# Connectors.net
KiCad netlist of a schematic drawn in Altium Designer
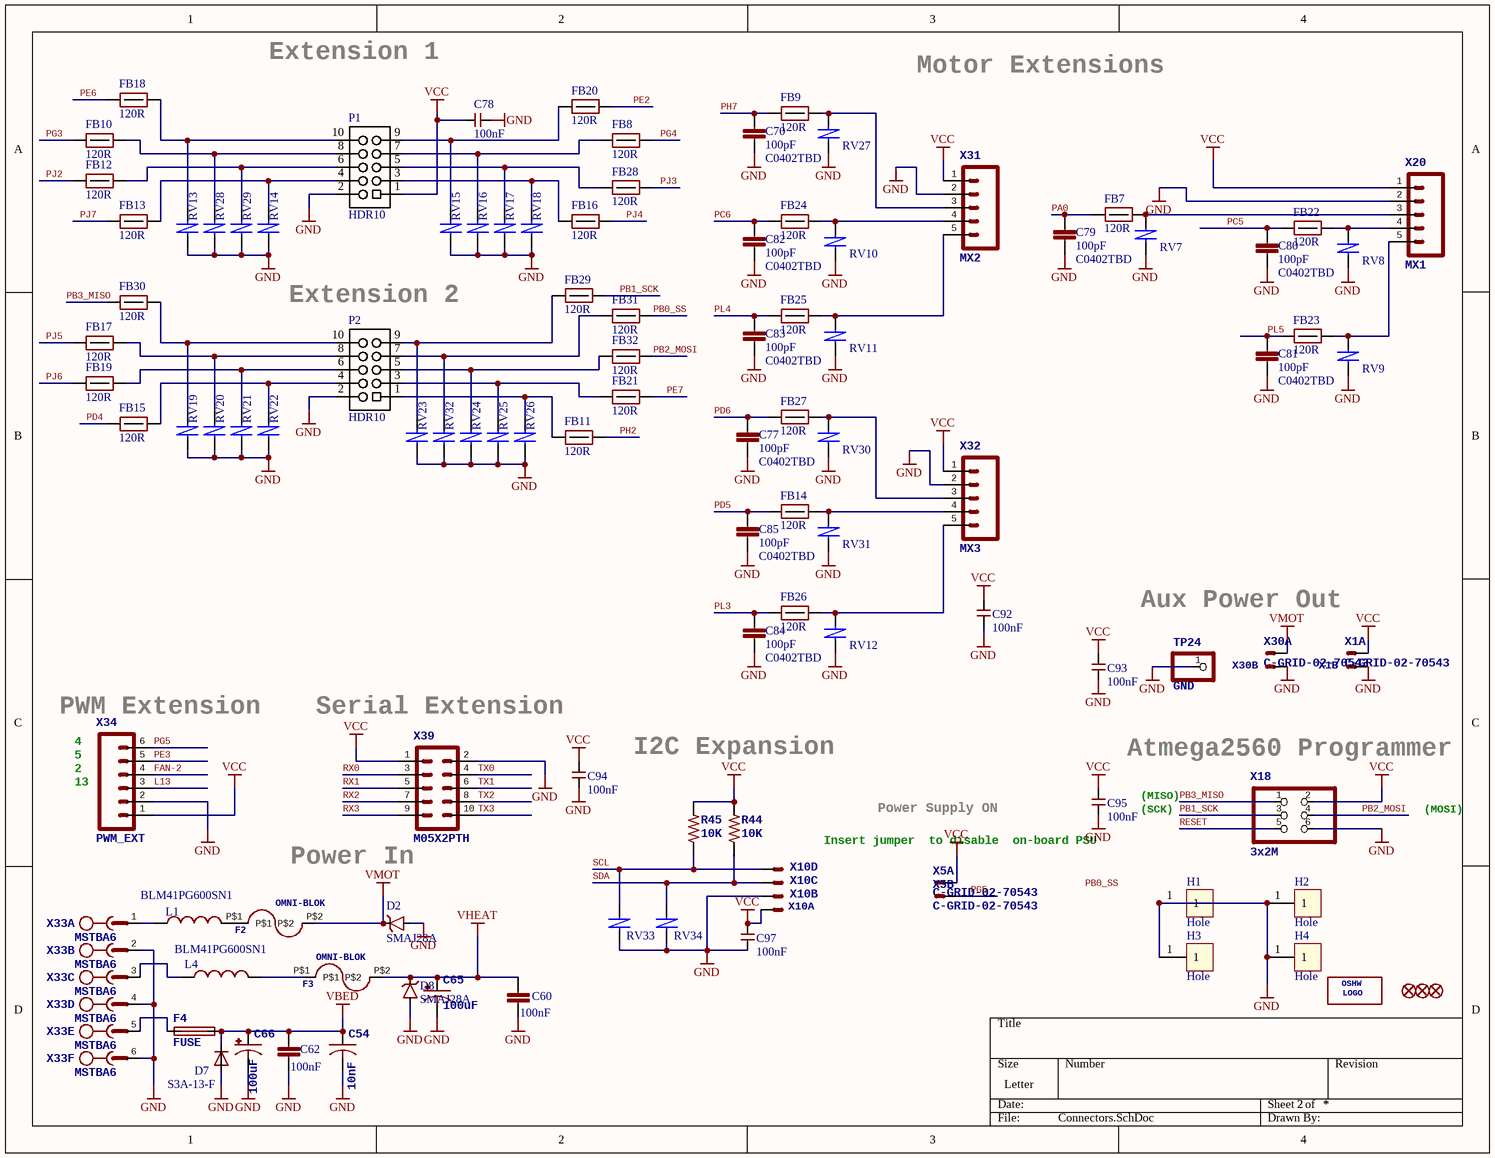
[diagram p0: Connectors.SchDoc]

(export (version "E")
  (design (tool "Eeschema 10.0.6"))
  (components
    (comp (ref "C54")
      (value "10nF")
      (footprint "C0603")
      (description "CAPACITOR, American symbol")
      (fields (field (name "MANUFACTURER") "TDK"))
      (libsource (lib "rcl") (part "C-USC0603"))
    )
    (comp (ref "C60")
      (value "100nF")
      (footprint "C0603")
      (description "CAP CER 0603 100nF 50V 10% X7R")
      (fields
        (field (name "MANUFACTURERPARTNUMBER") "C0603C104K5RACTU")
        (field (name "PUBLISHER") "UltiMachine")
      )
      (libsource (lib "3Delight") (part "C0603C104K5RACTU"))
    )
    (comp (ref "C62")
      (value "100nF")
      (footprint "C0603")
      (description "CAP CER 0603 100nF 50V 10% X7R")
      (fields
        (field (name "MANUFACTURERPARTNUMBER") "C0603C104K5RACTU")
        (field (name "PUBLISHER") "UltiMachine")
      )
      (libsource (lib "3Delight") (part "C0603C104K5RACTU"))
    )
    (comp (ref "C65")
      (value "100uF")
      (footprint "E3,5-8")
      (description "POLARIZED CAPACITOR, American symbol")
      (fields (field (name "MANUFACTURER") "Nichicon"))
      (libsource (lib "resistor") (part "CPOL-USE3.5-8"))
    )
    (comp (ref "C66")
      (value "100uF")
      (footprint "E3,5-8")
      (description "POLARIZED CAPACITOR, American symbol")
      (fields (field (name "MANUFACTURER") "Nichicon"))
      (libsource (lib "resistor") (part "CPOL-USE3.5-8"))
    )
    (comp (ref "C70")
      (value "100pF")
      (footprint "C0402")
      (description "Capacitor Non Polarized")
      (fields
        (field (name "MANUFACTURER") "Murata")
        (field (name "ALTIUM_VALUE") "C0402TBD")
        (field (name "PUBLISHER") "UltiMachine")
      )
      (libsource (lib "3Delight") (part "C0402TBD"))
    )
    (comp (ref "C77")
      (value "100pF")
      (footprint "C0402")
      (description "Capacitor Non Polarized")
      (fields
        (field (name "MANUFACTURER") "Murata")
        (field (name "ALTIUM_VALUE") "C0402TBD")
        (field (name "PUBLISHER") "UltiMachine")
      )
      (libsource (lib "3Delight") (part "C0402TBD"))
    )
    (comp (ref "C78")
      (value "100nF")
      (footprint "C0402")
      (description "CAP CER 0402 100nF 16V 10% X7R")
      (fields (field (name "MANUFACTURER") "Murata") (field (name "PART") "0.1uF 16V X7R 0402"))
      (libsource (lib "Capacitors") (part "100nF 0402 16V X7R"))
    )
    (comp (ref "C79")
      (value "100pF")
      (footprint "C0402")
      (description "Capacitor Non Polarized")
      (fields
        (field (name "MANUFACTURER") "Murata")
        (field (name "ALTIUM_VALUE") "C0402TBD")
        (field (name "PUBLISHER") "UltiMachine")
      )
      (libsource (lib "3Delight") (part "C0402TBD"))
    )
    (comp (ref "C80")
      (value "100pF")
      (footprint "C0402")
      (description "Capacitor Non Polarized")
      (fields
        (field (name "MANUFACTURER") "Murata")
        (field (name "ALTIUM_VALUE") "C0402TBD")
        (field (name "PUBLISHER") "UltiMachine")
      )
      (libsource (lib "3Delight") (part "C0402TBD"))
    )
    (comp (ref "C81")
      (value "100pF")
      (footprint "C0402")
      (description "Capacitor Non Polarized")
      (fields
        (field (name "MANUFACTURER") "Murata")
        (field (name "ALTIUM_VALUE") "C0402TBD")
        (field (name "PUBLISHER") "UltiMachine")
      )
      (libsource (lib "3Delight") (part "C0402TBD"))
    )
    (comp (ref "C82")
      (value "100pF")
      (footprint "C0402")
      (description "Capacitor Non Polarized")
      (fields
        (field (name "MANUFACTURER") "Murata")
        (field (name "ALTIUM_VALUE") "C0402TBD")
        (field (name "PUBLISHER") "UltiMachine")
      )
      (libsource (lib "3Delight") (part "C0402TBD"))
    )
    (comp (ref "C83")
      (value "100pF")
      (footprint "C0402")
      (description "Capacitor Non Polarized")
      (fields
        (field (name "MANUFACTURER") "Murata")
        (field (name "ALTIUM_VALUE") "C0402TBD")
        (field (name "PUBLISHER") "UltiMachine")
      )
      (libsource (lib "3Delight") (part "C0402TBD"))
    )
    (comp (ref "C84")
      (value "100pF")
      (footprint "C0402")
      (description "Capacitor Non Polarized")
      (fields
        (field (name "MANUFACTURER") "Murata")
        (field (name "ALTIUM_VALUE") "C0402TBD")
        (field (name "PUBLISHER") "UltiMachine")
      )
      (libsource (lib "3Delight") (part "C0402TBD"))
    )
    (comp (ref "C85")
      (value "100pF")
      (footprint "C0402")
      (description "Capacitor Non Polarized")
      (fields
        (field (name "MANUFACTURER") "Murata")
        (field (name "ALTIUM_VALUE") "C0402TBD")
        (field (name "PUBLISHER") "UltiMachine")
      )
      (libsource (lib "3Delight") (part "C0402TBD"))
    )
    (comp (ref "C92")
      (value "100nF")
      (footprint "C0402")
      (description "CAP CER 0402 100nF 16V 10% X7R")
      (fields (field (name "MANUFACTURER") "Murata") (field (name "PART") "0.1uF 16V X7R 0402"))
      (libsource (lib "Capacitors") (part "100nF 0402 16V X7R"))
    )
    (comp (ref "C93")
      (value "100nF")
      (footprint "C0402")
      (description "CAP CER 0402 100nF 16V 10% X7R")
      (fields (field (name "MANUFACTURER") "Murata") (field (name "PART") "0.1uF 16V X7R 0402"))
      (libsource (lib "Capacitors") (part "100nF 0402 16V X7R"))
    )
    (comp (ref "C94")
      (value "100nF")
      (footprint "C0402")
      (description "CAP CER 0402 100nF 16V 10% X7R")
      (fields (field (name "MANUFACTURER") "Murata") (field (name "PART") "0.1uF 16V X7R 0402"))
      (libsource (lib "Capacitors") (part "100nF 0402 16V X7R"))
    )
    (comp (ref "C95")
      (value "100nF")
      (footprint "C0402")
      (description "CAP CER 0402 100nF 16V 10% X7R")
      (fields (field (name "MANUFACTURER") "Murata") (field (name "PART") "0.1uF 16V X7R 0402"))
      (libsource (lib "Capacitors") (part "100nF 0402 16V X7R"))
    )
    (comp (ref "C97")
      (value "100nF")
      (footprint "C0402")
      (description "CAP CER 0402 100nF 16V 10% X7R")
      (fields (field (name "MANUFACTURER") "Murata") (field (name "PART") "0.1uF 16V X7R 0402"))
      (libsource (lib "Capacitors") (part "100nF 0402 16V X7R"))
    )
    (comp (ref "D2")
      (value "SMAJ28A")
      (footprint "Passives:SMA-SM")
      (description "TVS DIODE 28VWM 45.4VC SMA")
      (fields (field (name "MANUFACTURER") "Diodes Inc") (field (name "TOLERANCE") "NA"))
      (libsource (lib "Diodes") (part "SMAJ28A"))
    )
    (comp (ref "D7")
      (value "S3A-13-F")
      (footprint "DO-214AB")
      (description "DIODE DO-214AB")
      (fields (field (name "PUBLISHER") "UltiMachine"))
      (libsource (lib "3Delight") (part "S3A-13-F"))
    )
    (comp (ref "D8")
      (value "SMAJ28A")
      (footprint "Passives:SMA-SM")
      (description "TVS DIODE 28VWM 45.4VC SMA")
      (fields (field (name "MANUFACTURER") "Diodes Inc") (field (name "TOLERANCE") "NA"))
      (libsource (lib "Diodes") (part "SMAJ28A"))
    )
    (comp (ref "F2")
      (value "OMNI-BLOK")
      (footprint "OMNI-BLOK")
      (fields (field (name "MANUFACTURER") "Littlefuse"))
      (libsource (lib "ultimachine1") (part "OMNI-BLOK"))
    )
    (comp (ref "F3")
      (value "OMNI-BLOK")
      (footprint "OMNI-BLOK")
      (fields (field (name "MANUFACTURER") "Littlefuse"))
      (libsource (lib "ultimachine1") (part "OMNI-BLOK"))
    )
    (comp (ref "F4")
      (value "FUSE")
      (footprint "FUSE-ATO-SMD")
      (fields (field (name "MANUFACTURER") "Keystone"))
      (libsource (lib "RepRapjr (3)") (part "FUSE"))
    )
    (comp (ref "FB7")
      (value "120R")
      (footprint "R0402")
      (description "FERRITE BEAD 120 OHM 0402 1LN")
      (fields (field (name "MANUFACTURER") "Taiyo Yuden") (field (name "PART") "FERRITE 120R 1A 0402"))
      (libsource (lib "Inductors_1") (part "FERRITE 120R 1A 0402"))
    )
    (comp (ref "FB8")
      (value "120R")
      (footprint "R0402")
      (description "FERRITE BEAD 120 OHM 0402 1LN")
      (fields (field (name "MANUFACTURER") "Taiyo Yuden") (field (name "PART") "FERRITE 120R 1A 0402"))
      (libsource (lib "Inductors_1") (part "FERRITE 120R 1A 0402"))
    )
    (comp (ref "FB9")
      (value "120R")
      (footprint "R0402")
      (description "FERRITE BEAD 120 OHM 0402 1LN")
      (fields (field (name "MANUFACTURER") "Taiyo Yuden") (field (name "PART") "FERRITE 120R 1A 0402"))
      (libsource (lib "Inductors_1") (part "FERRITE 120R 1A 0402"))
    )
    (comp (ref "FB10")
      (value "120R")
      (footprint "R0402")
      (description "FERRITE BEAD 120 OHM 0402 1LN")
      (fields (field (name "MANUFACTURER") "Taiyo Yuden") (field (name "PART") "FERRITE 120R 1A 0402"))
      (libsource (lib "Inductors_1") (part "FERRITE 120R 1A 0402"))
    )
    (comp (ref "FB11")
      (value "120R")
      (footprint "R0402")
      (description "FERRITE BEAD 120 OHM 0402 1LN")
      (fields (field (name "MANUFACTURER") "Taiyo Yuden") (field (name "PART") "FERRITE 120R 1A 0402"))
      (libsource (lib "Inductors_1") (part "FERRITE 120R 1A 0402"))
    )
    (comp (ref "FB12")
      (value "120R")
      (footprint "R0402")
      (description "FERRITE BEAD 120 OHM 0402 1LN")
      (fields (field (name "MANUFACTURER") "Taiyo Yuden") (field (name "PART") "FERRITE 120R 1A 0402"))
      (libsource (lib "Inductors_1") (part "FERRITE 120R 1A 0402"))
    )
    (comp (ref "FB13")
      (value "120R")
      (footprint "R0402")
      (description "FERRITE BEAD 120 OHM 0402 1LN")
      (fields (field (name "MANUFACTURER") "Taiyo Yuden") (field (name "PART") "FERRITE 120R 1A 0402"))
      (libsource (lib "Inductors_1") (part "FERRITE 120R 1A 0402"))
    )
    (comp (ref "FB14")
      (value "120R")
      (footprint "R0402")
      (description "FERRITE BEAD 120 OHM 0402 1LN")
      (fields (field (name "MANUFACTURER") "Taiyo Yuden") (field (name "PART") "FERRITE 120R 1A 0402"))
      (libsource (lib "Inductors_1") (part "FERRITE 120R 1A 0402"))
    )
    (comp (ref "FB15")
      (value "120R")
      (footprint "R0402")
      (description "FERRITE BEAD 120 OHM 0402 1LN")
      (fields (field (name "MANUFACTURER") "Taiyo Yuden") (field (name "PART") "FERRITE 120R 1A 0402"))
      (libsource (lib "Inductors_1") (part "FERRITE 120R 1A 0402"))
    )
    (comp (ref "FB16")
      (value "120R")
      (footprint "R0402")
      (description "FERRITE BEAD 120 OHM 0402 1LN")
      (fields (field (name "MANUFACTURER") "Taiyo Yuden") (field (name "PART") "FERRITE 120R 1A 0402"))
      (libsource (lib "Inductors_1") (part "FERRITE 120R 1A 0402"))
    )
    (comp (ref "FB17")
      (value "120R")
      (footprint "R0402")
      (description "FERRITE BEAD 120 OHM 0402 1LN")
      (fields (field (name "MANUFACTURER") "Taiyo Yuden") (field (name "PART") "FERRITE 120R 1A 0402"))
      (libsource (lib "Inductors_1") (part "FERRITE 120R 1A 0402"))
    )
    (comp (ref "FB18")
      (value "120R")
      (footprint "R0402")
      (description "FERRITE BEAD 120 OHM 0402 1LN")
      (fields (field (name "MANUFACTURER") "Taiyo Yuden") (field (name "PART") "FERRITE 120R 1A 0402"))
      (libsource (lib "Inductors_1") (part "FERRITE 120R 1A 0402"))
    )
    (comp (ref "FB19")
      (value "120R")
      (footprint "R0402")
      (description "FERRITE BEAD 120 OHM 0402 1LN")
      (fields (field (name "MANUFACTURER") "Taiyo Yuden") (field (name "PART") "FERRITE 120R 1A 0402"))
      (libsource (lib "Inductors_1") (part "FERRITE 120R 1A 0402"))
    )
    (comp (ref "FB20")
      (value "120R")
      (footprint "R0402")
      (description "FERRITE BEAD 120 OHM 0402 1LN")
      (fields (field (name "MANUFACTURER") "Taiyo Yuden") (field (name "PART") "FERRITE 120R 1A 0402"))
      (libsource (lib "Inductors_1") (part "FERRITE 120R 1A 0402"))
    )
    (comp (ref "FB21")
      (value "120R")
      (footprint "R0402")
      (description "FERRITE BEAD 120 OHM 0402 1LN")
      (fields (field (name "MANUFACTURER") "Taiyo Yuden") (field (name "PART") "FERRITE 120R 1A 0402"))
      (libsource (lib "Inductors_1") (part "FERRITE 120R 1A 0402"))
    )
    (comp (ref "FB22")
      (value "120R")
      (footprint "R0402")
      (description "FERRITE BEAD 120 OHM 0402 1LN")
      (fields (field (name "MANUFACTURER") "Taiyo Yuden") (field (name "PART") "FERRITE 120R 1A 0402"))
      (libsource (lib "Inductors_1") (part "FERRITE 120R 1A 0402"))
    )
    (comp (ref "FB23")
      (value "120R")
      (footprint "R0402")
      (description "FERRITE BEAD 120 OHM 0402 1LN")
      (fields (field (name "MANUFACTURER") "Taiyo Yuden") (field (name "PART") "FERRITE 120R 1A 0402"))
      (libsource (lib "Inductors_1") (part "FERRITE 120R 1A 0402"))
    )
    (comp (ref "FB24")
      (value "120R")
      (footprint "R0402")
      (description "FERRITE BEAD 120 OHM 0402 1LN")
      (fields (field (name "MANUFACTURER") "Taiyo Yuden") (field (name "PART") "FERRITE 120R 1A 0402"))
      (libsource (lib "Inductors_1") (part "FERRITE 120R 1A 0402"))
    )
    (comp (ref "FB25")
      (value "120R")
      (footprint "R0402")
      (description "FERRITE BEAD 120 OHM 0402 1LN")
      (fields (field (name "MANUFACTURER") "Taiyo Yuden") (field (name "PART") "FERRITE 120R 1A 0402"))
      (libsource (lib "Inductors_1") (part "FERRITE 120R 1A 0402"))
    )
    (comp (ref "FB26")
      (value "120R")
      (footprint "R0402")
      (description "FERRITE BEAD 120 OHM 0402 1LN")
      (fields (field (name "MANUFACTURER") "Taiyo Yuden") (field (name "PART") "FERRITE 120R 1A 0402"))
      (libsource (lib "Inductors_1") (part "FERRITE 120R 1A 0402"))
    )
    (comp (ref "FB27")
      (value "120R")
      (footprint "R0402")
      (description "FERRITE BEAD 120 OHM 0402 1LN")
      (fields (field (name "MANUFACTURER") "Taiyo Yuden") (field (name "PART") "FERRITE 120R 1A 0402"))
      (libsource (lib "Inductors_1") (part "FERRITE 120R 1A 0402"))
    )
    (comp (ref "FB28")
      (value "120R")
      (footprint "R0402")
      (description "FERRITE BEAD 120 OHM 0402 1LN")
      (fields (field (name "MANUFACTURER") "Taiyo Yuden") (field (name "PART") "FERRITE 120R 1A 0402"))
      (libsource (lib "Inductors_1") (part "FERRITE 120R 1A 0402"))
    )
    (comp (ref "FB29")
      (value "120R")
      (footprint "R0402")
      (description "FERRITE BEAD 120 OHM 0402 1LN")
      (fields (field (name "MANUFACTURER") "Taiyo Yuden") (field (name "PART") "FERRITE 120R 1A 0402"))
      (libsource (lib "Inductors_1") (part "FERRITE 120R 1A 0402"))
    )
    (comp (ref "FB30")
      (value "120R")
      (footprint "R0402")
      (description "FERRITE BEAD 120 OHM 0402 1LN")
      (fields (field (name "MANUFACTURER") "Taiyo Yuden") (field (name "PART") "FERRITE 120R 1A 0402"))
      (libsource (lib "Inductors_1") (part "FERRITE 120R 1A 0402"))
    )
    (comp (ref "FB31")
      (value "120R")
      (footprint "R0402")
      (description "FERRITE BEAD 120 OHM 0402 1LN")
      (fields (field (name "MANUFACTURER") "Taiyo Yuden") (field (name "PART") "FERRITE 120R 1A 0402"))
      (libsource (lib "Inductors_1") (part "FERRITE 120R 1A 0402"))
    )
    (comp (ref "FB32")
      (value "120R")
      (footprint "R0402")
      (description "FERRITE BEAD 120 OHM 0402 1LN")
      (fields (field (name "MANUFACTURER") "Taiyo Yuden") (field (name "PART") "FERRITE 120R 1A 0402"))
      (libsource (lib "Inductors_1") (part "FERRITE 120R 1A 0402"))
    )
    (comp (ref "FID1")
      (value "FIDUCIAL1X2.5")
      (footprint "FIDUCIAL-1X2.5")
      (description "Fiducial Alignment PointsVarious fiducial points for machine vision alignment.")
      (libsource (lib "SparkFun") (part "FIDUCIAL1X2.5"))
    )
    (comp (ref "FID2")
      (value "FIDUCIAL1X2.5")
      (footprint "FIDUCIAL-1X2.5")
      (description "Fiducial Alignment PointsVarious fiducial points for machine vision alignment.")
      (libsource (lib "SparkFun") (part "FIDUCIAL1X2.5"))
    )
    (comp (ref "FID3")
      (value "FIDUCIAL1X2.5")
      (footprint "FIDUCIAL-1X2.5")
      (description "Fiducial Alignment PointsVarious fiducial points for machine vision alignment.")
      (libsource (lib "SparkFun") (part "FIDUCIAL1X2.5"))
    )
    (comp (ref "H1")
      (value "Hole")
      (footprint "Wave_hole_3x7-singleSided")
      (libsource (lib "3Delight") (part "Hole"))
    )
    (comp (ref "H2")
      (value "Hole")
      (footprint "Wave_hole_3x7-singleSided")
      (libsource (lib "3Delight") (part "Hole"))
    )
    (comp (ref "H3")
      (value "Hole")
      (footprint "Wave_hole_3x7-singleSided")
      (libsource (lib "3Delight") (part "Hole"))
    )
    (comp (ref "H4")
      (value "Hole")
      (footprint "Wave_hole_3x7-singleSided")
      (libsource (lib "3Delight") (part "Hole"))
    )
    (comp (ref "L1")
      (value "BLM41PG600SN1")
      (footprint "3Delight:L1806")
      (description "FERRITE BEAD 1806 60ohm")
      (fields
        (field (name "MANUFACTURERPARTNUMBER") "BLM41PG600SN1L")
        (field (name "PUBLISHER") "UltiMachine")
      )
      (libsource (lib "Inductors") (part "BLM41PG600SN1L"))
    )
    (comp (ref "L4")
      (value "BLM41PG600SN1")
      (footprint "3Delight:L1806")
      (description "FERRITE BEAD 1806 60ohm")
      (fields
        (field (name "MANUFACTURERPARTNUMBER") "BLM41PG600SN1L")
        (field (name "PUBLISHER") "UltiMachine")
      )
      (libsource (lib "Inductors") (part "BLM41PG600SN1L"))
    )
    (comp (ref "LOGO1")
      (value "OSHW_LOGO_8MILX0150-NT")
      (footprint "OSHW_8X150_NOTEXT")
      (fields (field (name "OSHW") "OSHW") (field (name "LOGO") "LOGO"))
      (libsource (lib "ohw-logo") (part "OSHW_LOGO_8MILX0150-NT"))
    )
    (comp (ref "P1")
      (value "HDR10")
      (footprint "HDR2X5 IDC")
      (description "CONN HEADER VERT 10POS GOLD")
      (fields (field (name "MANUFACTURER") "On Shore") (field (name "TOLERANCE") "-NA-"))
      (libsource (lib "Connectors") (part "Header 10PIN 2ROW T-HOLE VERT SHROUDED"))
    )
    (comp (ref "P2")
      (value "HDR10")
      (footprint "HDR2X5 IDC")
      (description "CONN HEADER VERT 10POS GOLD")
      (fields (field (name "MANUFACTURER") "On Shore") (field (name "TOLERANCE") "-NA-"))
      (libsource (lib "Connectors") (part "Header 10PIN 2ROW T-HOLE VERT SHROUDED"))
    )
    (comp (ref "R44")
      (value "10K")
      (footprint "R0603")
      (description "RESISTOR, American symbol")
      (fields (field (name "MANUFACTURER") "Panasonic"))
      (libsource (lib "resistor") (part "R-US_R0603"))
    )
    (comp (ref "R45")
      (value "10K")
      (footprint "R0603")
      (description "RESISTOR, American symbol")
      (fields (field (name "MANUFACTURER") "Panasonic"))
      (libsource (lib "resistor") (part "R-US_R0603"))
    )
    (comp (ref "RV7")
      (value "VRS0402SR55R101N")
      (footprint "C0402")
      (description "Multi-Layer Varistor")
      (fields (field (name "MANUFACTURER") "Yageo") (field (name "PART") "12V"))
      (libsource (lib "3Delight") (part "VRS0402SR55R101N"))
    )
    (comp (ref "RV8")
      (value "VRS0402SR55R101N")
      (footprint "C0402")
      (description "Multi-Layer Varistor")
      (fields (field (name "MANUFACTURER") "Yageo") (field (name "PART") "12V"))
      (libsource (lib "3Delight") (part "VRS0402SR55R101N"))
    )
    (comp (ref "RV9")
      (value "VRS0402SR55R101N")
      (footprint "C0402")
      (description "Multi-Layer Varistor")
      (fields (field (name "MANUFACTURER") "Yageo") (field (name "PART") "12V"))
      (libsource (lib "3Delight") (part "VRS0402SR55R101N"))
    )
    (comp (ref "RV10")
      (value "VRS0402SR55R101N")
      (footprint "C0402")
      (description "Multi-Layer Varistor")
      (fields (field (name "MANUFACTURER") "Yageo") (field (name "PART") "12V"))
      (libsource (lib "3Delight") (part "VRS0402SR55R101N"))
    )
    (comp (ref "RV11")
      (value "VRS0402SR55R101N")
      (footprint "C0402")
      (description "Multi-Layer Varistor")
      (fields (field (name "MANUFACTURER") "Yageo") (field (name "PART") "12V"))
      (libsource (lib "3Delight") (part "VRS0402SR55R101N"))
    )
    (comp (ref "RV12")
      (value "VRS0402SR55R101N")
      (footprint "C0402")
      (description "Multi-Layer Varistor")
      (fields (field (name "MANUFACTURER") "Yageo") (field (name "PART") "12V"))
      (libsource (lib "3Delight") (part "VRS0402SR55R101N"))
    )
    (comp (ref "RV13")
      (value "VRS0402SR55R101N")
      (footprint "C0402")
      (description "Multi-Layer Varistor")
      (fields (field (name "MANUFACTURER") "Yageo") (field (name "PART") "12V"))
      (libsource (lib "3Delight") (part "VRS0402SR55R101N"))
    )
    (comp (ref "RV14")
      (value "VRS0402SR55R101N")
      (footprint "C0402")
      (description "Multi-Layer Varistor")
      (fields (field (name "MANUFACTURER") "Yageo") (field (name "PART") "12V"))
      (libsource (lib "3Delight") (part "VRS0402SR55R101N"))
    )
    (comp (ref "RV15")
      (value "VRS0402SR55R101N")
      (footprint "C0402")
      (description "Multi-Layer Varistor")
      (fields (field (name "MANUFACTURER") "Yageo") (field (name "PART") "12V"))
      (libsource (lib "3Delight") (part "VRS0402SR55R101N"))
    )
    (comp (ref "RV16")
      (value "VRS0402SR55R101N")
      (footprint "C0402")
      (description "Multi-Layer Varistor")
      (fields (field (name "MANUFACTURER") "Yageo") (field (name "PART") "12V"))
      (libsource (lib "3Delight") (part "VRS0402SR55R101N"))
    )
    (comp (ref "RV17")
      (value "VRS0402SR55R101N")
      (footprint "C0402")
      (description "Multi-Layer Varistor")
      (fields (field (name "MANUFACTURER") "Yageo") (field (name "PART") "12V"))
      (libsource (lib "3Delight") (part "VRS0402SR55R101N"))
    )
    (comp (ref "RV18")
      (value "VRS0402SR55R101N")
      (footprint "C0402")
      (description "Multi-Layer Varistor")
      (fields (field (name "MANUFACTURER") "Yageo") (field (name "PART") "12V"))
      (libsource (lib "3Delight") (part "VRS0402SR55R101N"))
    )
    (comp (ref "RV19")
      (value "VRS0402SR55R101N")
      (footprint "C0402")
      (description "Multi-Layer Varistor")
      (fields (field (name "MANUFACTURER") "Yageo") (field (name "PART") "12V"))
      (libsource (lib "3Delight") (part "VRS0402SR55R101N"))
    )
    (comp (ref "RV20")
      (value "VRS0402SR55R101N")
      (footprint "C0402")
      (description "Multi-Layer Varistor")
      (fields (field (name "MANUFACTURER") "Yageo") (field (name "PART") "12V"))
      (libsource (lib "3Delight") (part "VRS0402SR55R101N"))
    )
    (comp (ref "RV21")
      (value "VRS0402SR55R101N")
      (footprint "C0402")
      (description "Multi-Layer Varistor")
      (fields (field (name "MANUFACTURER") "Yageo") (field (name "PART") "12V"))
      (libsource (lib "3Delight") (part "VRS0402SR55R101N"))
    )
    (comp (ref "RV22")
      (value "VRS0402SR55R101N")
      (footprint "C0402")
      (description "Multi-Layer Varistor")
      (fields (field (name "MANUFACTURER") "Yageo") (field (name "PART") "12V"))
      (libsource (lib "3Delight") (part "VRS0402SR55R101N"))
    )
    (comp (ref "RV23")
      (value "VRS0402SR55R101N")
      (footprint "C0402")
      (description "Multi-Layer Varistor")
      (fields (field (name "MANUFACTURER") "Yageo") (field (name "PART") "12V"))
      (libsource (lib "3Delight") (part "VRS0402SR55R101N"))
    )
    (comp (ref "RV24")
      (value "VRS0402SR55R101N")
      (footprint "C0402")
      (description "Multi-Layer Varistor")
      (fields (field (name "MANUFACTURER") "Yageo") (field (name "PART") "12V"))
      (libsource (lib "3Delight") (part "VRS0402SR55R101N"))
    )
    (comp (ref "RV25")
      (value "VRS0402SR55R101N")
      (footprint "C0402")
      (description "Multi-Layer Varistor")
      (fields (field (name "MANUFACTURER") "Yageo") (field (name "PART") "12V"))
      (libsource (lib "3Delight") (part "VRS0402SR55R101N"))
    )
    (comp (ref "RV26")
      (value "VRS0402SR55R101N")
      (footprint "C0402")
      (description "Multi-Layer Varistor")
      (fields (field (name "MANUFACTURER") "Yageo") (field (name "PART") "12V"))
      (libsource (lib "3Delight") (part "VRS0402SR55R101N"))
    )
    (comp (ref "RV27")
      (value "VRS0402SR55R101N")
      (footprint "C0402")
      (description "Multi-Layer Varistor")
      (fields (field (name "MANUFACTURER") "Yageo") (field (name "PART") "12V"))
      (libsource (lib "3Delight") (part "VRS0402SR55R101N"))
    )
    (comp (ref "RV28")
      (value "VRS0402SR55R101N")
      (footprint "C0402")
      (description "Multi-Layer Varistor")
      (fields (field (name "MANUFACTURER") "Yageo") (field (name "PART") "12V"))
      (libsource (lib "3Delight") (part "VRS0402SR55R101N"))
    )
    (comp (ref "RV29")
      (value "VRS0402SR55R101N")
      (footprint "C0402")
      (description "Multi-Layer Varistor")
      (fields (field (name "MANUFACTURER") "Yageo") (field (name "PART") "12V"))
      (libsource (lib "3Delight") (part "VRS0402SR55R101N"))
    )
    (comp (ref "RV30")
      (value "VRS0402SR55R101N")
      (footprint "C0402")
      (description "Multi-Layer Varistor")
      (fields (field (name "MANUFACTURER") "Yageo") (field (name "PART") "12V"))
      (libsource (lib "3Delight") (part "VRS0402SR55R101N"))
    )
    (comp (ref "RV31")
      (value "VRS0402SR55R101N")
      (footprint "C0402")
      (description "Multi-Layer Varistor")
      (fields (field (name "MANUFACTURER") "Yageo") (field (name "PART") "12V"))
      (libsource (lib "3Delight") (part "VRS0402SR55R101N"))
    )
    (comp (ref "RV32")
      (value "VRS0402SR55R101N")
      (footprint "C0402")
      (description "Multi-Layer Varistor")
      (fields (field (name "MANUFACTURER") "Yageo") (field (name "PART") "12V"))
      (libsource (lib "3Delight") (part "VRS0402SR55R101N"))
    )
    (comp (ref "RV33")
      (value "VRS0402SR55R101N")
      (footprint "C0402")
      (description "Multi-Layer Varistor")
      (fields (field (name "MANUFACTURER") "Yageo") (field (name "PART") "12V"))
      (libsource (lib "3Delight") (part "VRS0402SR55R101N"))
    )
    (comp (ref "RV34")
      (value "VRS0402SR55R101N")
      (footprint "C0402")
      (description "Multi-Layer Varistor")
      (fields (field (name "MANUFACTURER") "Yageo") (field (name "PART") "12V"))
      (libsource (lib "3Delight") (part "VRS0402SR55R101N"))
    )
    (comp (ref "TP24")
      (value "GND")
      (footprint "1X01")
      (description "Pin header 1x1 for 0.1\" spacing   With round pins")
      (libsource (lib "adafruit") (part "PINHD-1X1"))
    )
    (comp (ref "X1")
      (value "C-GRID-02-70543")
      (footprint "70543-02")
      (description "CONNECTOR   wire to board 2.54 mm (0.100\") pitch header")
      (fields (field (name "MANUFACTURER") "Molex"))
      (libsource (lib "con-molex") (part "C-GRID-02-70543"))
    )
    (comp (ref "X5")
      (value "C-GRID-02-70543")
      (footprint "70543-02")
      (description "CONNECTOR   wire to board 2.54 mm (0.100\") pitch header")
      (fields (field (name "MANUFACTURER") "Molex"))
      (libsource (lib "con-molex") (part "C-GRID-02-70543"))
    )
    (comp (ref "X10")
      (value "C-GRID-04-70543")
      (footprint "70543-04")
      (description "CONNECTOR   wire to board 2.54 mm (0.100\") pitch header")
      (fields (field (name "MANUFACTURER") "Molex"))
      (libsource (lib "con-molex") (part "C-GRID-04-70543"))
    )
    (comp (ref "X18")
      (value "3x2M")
      (footprint "2X03")
      (description "PIN HEADER")
      (libsource (lib "SmartPrj") (part "PINHD-2X3"))
    )
    (comp (ref "X20") (value "MX1") (footprint "1X05") (libsource (lib "SparkFun") (part "M05PTH")))
    (comp (ref "X30")
      (value "C-GRID-02-70543")
      (footprint "70543-02")
      (description "CONNECTOR   wire to board 2.54 mm (0.100\") pitch header")
      (fields (field (name "MANUFACTURER") "Molex"))
      (libsource (lib "con-molex") (part "C-GRID-02-70543"))
    )
    (comp (ref "X31") (value "MX2") (footprint "1X05") (libsource (lib "SparkFun") (part "M05PTH")))
    (comp (ref "X32") (value "MX3") (footprint "1X05") (libsource (lib "SparkFun") (part "M05PTH")))
    (comp (ref "X33")
      (value "MSTBA6")
      (footprint "MSTBA6")
      (description "PHOENIX")
      (fields (field (name "MF") "FARNELL") (field (name "MPN") "1757284"))
      (libsource (lib "con-phoenix-508") (part "MSTBA6"))
    )
    (comp (ref "X34") (value "PWM_EXT") (footprint "1X06") (libsource (lib "SparkFun") (part "M06SIP")))
    (comp (ref "X39")
      (value "M05X2PTH")
      (footprint "AVR_ICSP")
      (libsource (lib "SparkFun") (part "M05X2PTH"))
    )
  )
  (nets
    (net (code "1") (name "/FAN-2") (class "Default")
      (node (ref "X34") (pin "4") (pinfunction "4_4") (pintype "passive"))
    )
    (net (code "2") (name "/L13") (class "Default")
      (node (ref "X34") (pin "3") (pinfunction "3_3") (pintype "passive"))
    )
    (net (code "3") (name "/PA0") (class "Default")
      (node (ref "C79") (pin "1") (pinfunction "1_1") (pintype "passive"))
      (node (ref "FB7") (pin "1") (pinfunction "1_1") (pintype "passive"))
    )
    (net (code "4") (name "/PB0_SS") (class "Default")
      (node (ref "FB31") (pin "1") (pinfunction "1_1") (pintype "passive"))
    )
    (net (code "5") (name "/PB1_SCK") (class "Default")
      (node (ref "FB29") (pin "1") (pinfunction "1_1") (pintype "passive"))
      (node (ref "X18") (pin "3") (pinfunction "3_3") (pintype "passive"))
    )
    (net (code "6") (name "/PB2_MOSI") (class "Default")
      (node (ref "FB32") (pin "1") (pinfunction "1_1") (pintype "passive"))
      (node (ref "X18") (pin "4") (pinfunction "4_4") (pintype "passive"))
    )
    (net (code "7") (name "/PB3_MISO") (class "Default")
      (node (ref "FB30") (pin "2") (pinfunction "2_2") (pintype "passive"))
      (node (ref "X18") (pin "1") (pinfunction "1_1") (pintype "passive"))
    )
    (net (code "8") (name "/PC5") (class "Default")
      (node (ref "C80") (pin "1") (pinfunction "1_1") (pintype "passive"))
      (node (ref "FB22") (pin "1") (pinfunction "1_1") (pintype "passive"))
    )
    (net (code "9") (name "/PC6") (class "Default")
      (node (ref "C82") (pin "1") (pinfunction "1_1") (pintype "passive"))
      (node (ref "FB24") (pin "1") (pinfunction "1_1") (pintype "passive"))
    )
    (net (code "10") (name "/PD4") (class "Default")
      (node (ref "FB15") (pin "2") (pinfunction "2_2") (pintype "passive"))
    )
    (net (code "11") (name "/PD5") (class "Default")
      (node (ref "C85") (pin "1") (pinfunction "1_1") (pintype "passive"))
      (node (ref "FB14") (pin "2") (pinfunction "2_2") (pintype "passive"))
    )
    (net (code "12") (name "/PD6") (class "Default")
      (node (ref "C77") (pin "1") (pinfunction "1_1") (pintype "passive"))
      (node (ref "FB27") (pin "2") (pinfunction "2_2") (pintype "passive"))
    )
    (net (code "13") (name "/PE2") (class "Default")
      (node (ref "FB20") (pin "2") (pinfunction "2_2") (pintype "passive"))
    )
    (net (code "14") (name "/PE3") (class "Default")
      (node (ref "X34") (pin "5") (pinfunction "5_5") (pintype "passive"))
    )
    (net (code "15") (name "/PE6") (class "Default")
      (node (ref "FB18") (pin "2") (pinfunction "2_2") (pintype "passive"))
    )
    (net (code "16") (name "/PE7") (class "Default")
      (node (ref "FB21") (pin "1") (pinfunction "1_1") (pintype "passive"))
    )
    (net (code "17") (name "/PG3") (class "Default")
      (node (ref "FB10") (pin "1") (pinfunction "1_1") (pintype "passive"))
    )
    (net (code "18") (name "/PG4") (class "Default")
      (node (ref "FB8") (pin "1") (pinfunction "1_1") (pintype "passive"))
    )
    (net (code "19") (name "/PG5") (class "Default")
      (node (ref "X34") (pin "6") (pinfunction "6_6") (pintype "passive"))
      (node (ref "X5") (pin "1") (pinfunction "S_1") (pintype "passive"))
    )
    (net (code "20") (name "/PH2") (class "Default")
      (node (ref "FB11") (pin "1") (pinfunction "1_1") (pintype "passive"))
    )
    (net (code "21") (name "/PH7") (class "Default")
      (node (ref "C70") (pin "1") (pinfunction "1_1") (pintype "passive"))
      (node (ref "FB9") (pin "2") (pinfunction "2_2") (pintype "passive"))
    )
    (net (code "22") (name "/PJ2") (class "Default")
      (node (ref "FB12") (pin "1") (pinfunction "1_1") (pintype "passive"))
    )
    (net (code "23") (name "/PJ3") (class "Default")
      (node (ref "FB28") (pin "1") (pinfunction "1_1") (pintype "passive"))
    )
    (net (code "24") (name "/PJ4") (class "Default")
      (node (ref "FB16") (pin "1") (pinfunction "1_1") (pintype "passive"))
    )
    (net (code "25") (name "/PJ5") (class "Default")
      (node (ref "FB17") (pin "1") (pinfunction "1_1") (pintype "passive"))
    )
    (net (code "26") (name "/PJ6") (class "Default")
      (node (ref "FB19") (pin "1") (pinfunction "1_1") (pintype "passive"))
    )
    (net (code "27") (name "/PJ7") (class "Default")
      (node (ref "FB13") (pin "1") (pinfunction "1_1") (pintype "passive"))
    )
    (net (code "28") (name "/PL3") (class "Default")
      (node (ref "C84") (pin "1") (pinfunction "1_1") (pintype "passive"))
      (node (ref "FB26") (pin "1") (pinfunction "1_1") (pintype "passive"))
    )
    (net (code "29") (name "/PL4") (class "Default")
      (node (ref "C83") (pin "1") (pinfunction "1_1") (pintype "passive"))
      (node (ref "FB25") (pin "1") (pinfunction "1_1") (pintype "passive"))
    )
    (net (code "30") (name "/PL5") (class "Default")
      (node (ref "C81") (pin "1") (pinfunction "1_1") (pintype "passive"))
      (node (ref "FB23") (pin "1") (pinfunction "1_1") (pintype "passive"))
    )
    (net (code "31") (name "/RESET") (class "Default")
      (node (ref "X18") (pin "5") (pinfunction "5_5") (pintype "passive"))
    )
    (net (code "32") (name "/RX0") (class "Default")
      (node (ref "X39") (pin "3") (pinfunction "3_3") (pintype "passive"))
    )
    (net (code "33") (name "/RX1") (class "Default")
      (node (ref "X39") (pin "5") (pinfunction "5_5") (pintype "passive"))
    )
    (net (code "34") (name "/RX2") (class "Default")
      (node (ref "X39") (pin "7") (pinfunction "7_7") (pintype "passive"))
    )
    (net (code "35") (name "/RX3") (class "Default")
      (node (ref "X39") (pin "9") (pinfunction "9_9") (pintype "passive"))
    )
    (net (code "36") (name "/SCL") (class "Default")
      (node (ref "R45") (pin "1") (pinfunction "1_1") (pintype "passive"))
      (node (ref "RV33") (pin "2") (pinfunction "2_2") (pintype "passive"))
      (node (ref "X10") (pin "4") (pinfunction "S_4") (pintype "passive"))
    )
    (net (code "37") (name "/SDA") (class "Default")
      (node (ref "R44") (pin "1") (pinfunction "1_1") (pintype "passive"))
      (node (ref "RV34") (pin "2") (pinfunction "2_2") (pintype "passive"))
      (node (ref "X10") (pin "3") (pinfunction "S_3") (pintype "passive"))
    )
    (net (code "38") (name "/TX0") (class "Default")
      (node (ref "X39") (pin "4") (pinfunction "4_4") (pintype "passive"))
    )
    (net (code "39") (name "/TX1") (class "Default")
      (node (ref "X39") (pin "6") (pinfunction "6_6") (pintype "passive"))
    )
    (net (code "40") (name "/TX2") (class "Default")
      (node (ref "X39") (pin "8") (pinfunction "8_8") (pintype "passive"))
    )
    (net (code "41") (name "/TX3") (class "Default")
      (node (ref "X39") (pin "10") (pinfunction "10_10") (pintype "passive"))
    )
    (net (code "42") (name "GND") (class "Default")
      (node (ref "C54") (pin "2") (pinfunction "2_2") (pintype "passive"))
      (node (ref "C60") (pin "2") (pinfunction "2_2") (pintype "passive"))
      (node (ref "C62") (pin "2") (pinfunction "2_2") (pintype "passive"))
      (node (ref "C65") (pin "-") (pinfunction "-_-") (pintype "passive"))
      (node (ref "C66") (pin "-") (pinfunction "-_-") (pintype "passive"))
      (node (ref "C70") (pin "2") (pinfunction "2_2") (pintype "passive"))
      (node (ref "C77") (pin "2") (pinfunction "2_2") (pintype "passive"))
      (node (ref "C78") (pin "1") (pinfunction "1_1") (pintype "passive"))
      (node (ref "C79") (pin "2") (pinfunction "2_2") (pintype "passive"))
      (node (ref "C80") (pin "2") (pinfunction "2_2") (pintype "passive"))
      (node (ref "C81") (pin "2") (pinfunction "2_2") (pintype "passive"))
      (node (ref "C82") (pin "2") (pinfunction "2_2") (pintype "passive"))
      (node (ref "C83") (pin "2") (pinfunction "2_2") (pintype "passive"))
      (node (ref "C84") (pin "2") (pinfunction "2_2") (pintype "passive"))
      (node (ref "C85") (pin "2") (pinfunction "2_2") (pintype "passive"))
      (node (ref "C92") (pin "1") (pinfunction "1_1") (pintype "passive"))
      (node (ref "C93") (pin "1") (pinfunction "1_1") (pintype "passive"))
      (node (ref "C94") (pin "1") (pinfunction "1_1") (pintype "passive"))
      (node (ref "C95") (pin "1") (pinfunction "1_1") (pintype "passive"))
      (node (ref "C97") (pin "2") (pinfunction "2_2") (pintype "passive"))
      (node (ref "D2") (pin "A") (pinfunction "A_A") (pintype "passive"))
      (node (ref "D7") (pin "A") (pinfunction "A_A") (pintype "passive"))
      (node (ref "D8") (pin "A") (pinfunction "A_A") (pintype "passive"))
      (node (ref "H1") (pin "1") (pinfunction "1_1") (pintype "power_in"))
      (node (ref "H2") (pin "1") (pinfunction "1_1") (pintype "power_in"))
      (node (ref "H3") (pin "1") (pinfunction "1_1") (pintype "power_in"))
      (node (ref "H4") (pin "1") (pinfunction "1_1") (pintype "power_in"))
      (node (ref "P1") (pin "2") (pinfunction "2_2") (pintype "passive"))
      (node (ref "P2") (pin "2") (pinfunction "2_2") (pintype "passive"))
      (node (ref "RV10") (pin "1") (pinfunction "1_1") (pintype "passive"))
      (node (ref "RV11") (pin "1") (pinfunction "1_1") (pintype "passive"))
      (node (ref "RV12") (pin "1") (pinfunction "1_1") (pintype "passive"))
      (node (ref "RV13") (pin "2") (pinfunction "2_2") (pintype "passive"))
      (node (ref "RV14") (pin "2") (pinfunction "2_2") (pintype "passive"))
      (node (ref "RV15") (pin "2") (pinfunction "2_2") (pintype "passive"))
      (node (ref "RV16") (pin "1") (pinfunction "1_1") (pintype "passive"))
      (node (ref "RV17") (pin "2") (pinfunction "2_2") (pintype "passive"))
      (node (ref "RV18") (pin "1") (pinfunction "1_1") (pintype "passive"))
      (node (ref "RV19") (pin "2") (pinfunction "2_2") (pintype "passive"))
      (node (ref "RV20") (pin "2") (pinfunction "2_2") (pintype "passive"))
      (node (ref "RV21") (pin "2") (pinfunction "2_2") (pintype "passive"))
      (node (ref "RV22") (pin "2") (pinfunction "2_2") (pintype "passive"))
      (node (ref "RV23") (pin "1") (pinfunction "1_1") (pintype "passive"))
      (node (ref "RV24") (pin "1") (pinfunction "1_1") (pintype "passive"))
      (node (ref "RV25") (pin "1") (pinfunction "1_1") (pintype "passive"))
      (node (ref "RV26") (pin "1") (pinfunction "1_1") (pintype "passive"))
      (node (ref "RV27") (pin "1") (pinfunction "1_1") (pintype "passive"))
      (node (ref "RV28") (pin "2") (pinfunction "2_2") (pintype "passive"))
      (node (ref "RV29") (pin "2") (pinfunction "2_2") (pintype "passive"))
      (node (ref "RV30") (pin "1") (pinfunction "1_1") (pintype "passive"))
      (node (ref "RV31") (pin "1") (pinfunction "1_1") (pintype "passive"))
      (node (ref "RV32") (pin "1") (pinfunction "1_1") (pintype "passive"))
      (node (ref "RV33") (pin "1") (pinfunction "1_1") (pintype "passive"))
      (node (ref "RV34") (pin "1") (pinfunction "1_1") (pintype "passive"))
      (node (ref "RV7") (pin "1") (pinfunction "1_1") (pintype "passive"))
      (node (ref "RV8") (pin "1") (pinfunction "1_1") (pintype "passive"))
      (node (ref "RV9") (pin "1") (pinfunction "1_1") (pintype "passive"))
      (node (ref "TP24") (pin "1") (pinfunction "1_1") (pintype "passive"))
      (node (ref "X1") (pin "1") (pinfunction "S_1") (pintype "passive"))
      (node (ref "X10") (pin "2") (pinfunction "S_2") (pintype "passive"))
      (node (ref "X18") (pin "6") (pinfunction "6_6") (pintype "passive"))
      (node (ref "X20") (pin "2") (pinfunction "2_2") (pintype "passive"))
      (node (ref "X30") (pin "1") (pinfunction "S_1") (pintype "passive"))
      (node (ref "X31") (pin "2") (pinfunction "2_2") (pintype "passive"))
      (node (ref "X32") (pin "2") (pinfunction "2_2") (pintype "passive"))
      (node (ref "X33") (pin "2") (pinfunction "1_2") (pintype "passive"))
      (node (ref "X33") (pin "4") (pinfunction "1_4") (pintype "passive"))
      (node (ref "X33") (pin "6") (pinfunction "1_6") (pintype "passive"))
      (node (ref "X34") (pin "2") (pinfunction "2_2") (pintype "passive"))
      (node (ref "X39") (pin "2") (pinfunction "2_2") (pintype "passive"))
    )
    (net (code "43") (name "Net-(F2-PadP$1)") (class "Default")
      (node (ref "F2") (pin "P$1") (pinfunction "P$1_P$1") (pintype "passive"))
      (node (ref "L1") (pin "2") (pinfunction "2_2") (pintype "passive"))
    )
    (net (code "44") (name "Net-(F3-PadP$1)") (class "Default")
      (node (ref "F3") (pin "P$1") (pinfunction "P$1_P$1") (pintype "passive"))
      (node (ref "L4") (pin "2") (pinfunction "2_2") (pintype "passive"))
    )
    (net (code "45") (name "Net-(F4-1)") (class "Default")
      (node (ref "F4") (pin "P$1") (pinfunction "1_P$1") (pintype "passive"))
      (node (ref "X33") (pin "5") (pinfunction "1_5") (pintype "passive"))
    )
    (net (code "46") (name "Net-(FB7-Pad2)") (class "Default")
      (node (ref "FB7") (pin "2") (pinfunction "2_2") (pintype "passive"))
      (node (ref "RV7") (pin "2") (pinfunction "2_2") (pintype "passive"))
      (node (ref "X20") (pin "3") (pinfunction "3_3") (pintype "passive"))
    )
    (net (code "47") (name "Net-(FB8-Pad2)") (class "Default")
      (node (ref "FB8") (pin "2") (pinfunction "2_2") (pintype "passive"))
      (node (ref "P1") (pin "7") (pinfunction "7_7") (pintype "passive"))
      (node (ref "RV16") (pin "2") (pinfunction "2_2") (pintype "passive"))
    )
    (net (code "48") (name "Net-(FB9-Pad1)") (class "Default")
      (node (ref "FB9") (pin "1") (pinfunction "1_1") (pintype "passive"))
      (node (ref "RV27") (pin "2") (pinfunction "2_2") (pintype "passive"))
      (node (ref "X31") (pin "3") (pinfunction "3_3") (pintype "passive"))
    )
    (net (code "49") (name "Net-(FB10-Pad2)") (class "Default")
      (node (ref "FB10") (pin "2") (pinfunction "2_2") (pintype "passive"))
      (node (ref "P1") (pin "8") (pinfunction "8_8") (pintype "passive"))
      (node (ref "RV28") (pin "1") (pinfunction "1_1") (pintype "passive"))
    )
    (net (code "50") (name "Net-(FB11-Pad2)") (class "Default")
      (node (ref "FB11") (pin "2") (pinfunction "2_2") (pintype "passive"))
      (node (ref "P2") (pin "1") (pinfunction "1_1") (pintype "passive"))
      (node (ref "RV26") (pin "2") (pinfunction "2_2") (pintype "passive"))
    )
    (net (code "51") (name "Net-(FB12-Pad2)") (class "Default")
      (node (ref "FB12") (pin "2") (pinfunction "2_2") (pintype "passive"))
      (node (ref "P1") (pin "6") (pinfunction "6_6") (pintype "passive"))
      (node (ref "RV29") (pin "1") (pinfunction "1_1") (pintype "passive"))
    )
    (net (code "52") (name "Net-(FB13-Pad2)") (class "Default")
      (node (ref "FB13") (pin "2") (pinfunction "2_2") (pintype "passive"))
      (node (ref "P1") (pin "4") (pinfunction "4_4") (pintype "passive"))
      (node (ref "RV14") (pin "1") (pinfunction "1_1") (pintype "passive"))
    )
    (net (code "53") (name "Net-(FB14-Pad1)") (class "Default")
      (node (ref "FB14") (pin "1") (pinfunction "1_1") (pintype "passive"))
      (node (ref "RV31") (pin "2") (pinfunction "2_2") (pintype "passive"))
      (node (ref "X32") (pin "4") (pinfunction "4_4") (pintype "passive"))
    )
    (net (code "54") (name "Net-(FB15-Pad1)") (class "Default")
      (node (ref "FB15") (pin "1") (pinfunction "1_1") (pintype "passive"))
      (node (ref "P2") (pin "4") (pinfunction "4_4") (pintype "passive"))
      (node (ref "RV22") (pin "1") (pinfunction "1_1") (pintype "passive"))
    )
    (net (code "55") (name "Net-(FB16-Pad2)") (class "Default")
      (node (ref "FB16") (pin "2") (pinfunction "2_2") (pintype "passive"))
      (node (ref "P1") (pin "3") (pinfunction "3_3") (pintype "passive"))
      (node (ref "RV18") (pin "2") (pinfunction "2_2") (pintype "passive"))
    )
    (net (code "56") (name "Net-(FB17-Pad2)") (class "Default")
      (node (ref "FB17") (pin "2") (pinfunction "2_2") (pintype "passive"))
      (node (ref "P2") (pin "8") (pinfunction "8_8") (pintype "passive"))
      (node (ref "RV20") (pin "1") (pinfunction "1_1") (pintype "passive"))
    )
    (net (code "57") (name "Net-(FB18-Pad1)") (class "Default")
      (node (ref "FB18") (pin "1") (pinfunction "1_1") (pintype "passive"))
      (node (ref "P1") (pin "10") (pinfunction "10_10") (pintype "passive"))
      (node (ref "RV13") (pin "1") (pinfunction "1_1") (pintype "passive"))
    )
    (net (code "58") (name "Net-(FB19-Pad2)") (class "Default")
      (node (ref "FB19") (pin "2") (pinfunction "2_2") (pintype "passive"))
      (node (ref "P2") (pin "6") (pinfunction "6_6") (pintype "passive"))
      (node (ref "RV21") (pin "1") (pinfunction "1_1") (pintype "passive"))
    )
    (net (code "59") (name "Net-(FB20-Pad1)") (class "Default")
      (node (ref "FB20") (pin "1") (pinfunction "1_1") (pintype "passive"))
      (node (ref "P1") (pin "9") (pinfunction "9_9") (pintype "passive"))
      (node (ref "RV15") (pin "1") (pinfunction "1_1") (pintype "passive"))
    )
    (net (code "60") (name "Net-(FB21-Pad2)") (class "Default")
      (node (ref "FB21") (pin "2") (pinfunction "2_2") (pintype "passive"))
      (node (ref "P2") (pin "3") (pinfunction "3_3") (pintype "passive"))
      (node (ref "RV25") (pin "2") (pinfunction "2_2") (pintype "passive"))
    )
    (net (code "61") (name "Net-(FB22-Pad2)") (class "Default")
      (node (ref "FB22") (pin "2") (pinfunction "2_2") (pintype "passive"))
      (node (ref "RV8") (pin "2") (pinfunction "2_2") (pintype "passive"))
      (node (ref "X20") (pin "4") (pinfunction "4_4") (pintype "passive"))
    )
    (net (code "62") (name "Net-(FB23-Pad2)") (class "Default")
      (node (ref "FB23") (pin "2") (pinfunction "2_2") (pintype "passive"))
      (node (ref "RV9") (pin "2") (pinfunction "2_2") (pintype "passive"))
      (node (ref "X20") (pin "5") (pinfunction "5_5") (pintype "passive"))
    )
    (net (code "63") (name "Net-(FB24-Pad2)") (class "Default")
      (node (ref "FB24") (pin "2") (pinfunction "2_2") (pintype "passive"))
      (node (ref "RV10") (pin "2") (pinfunction "2_2") (pintype "passive"))
      (node (ref "X31") (pin "4") (pinfunction "4_4") (pintype "passive"))
    )
    (net (code "64") (name "Net-(FB25-Pad2)") (class "Default")
      (node (ref "FB25") (pin "2") (pinfunction "2_2") (pintype "passive"))
      (node (ref "RV11") (pin "2") (pinfunction "2_2") (pintype "passive"))
      (node (ref "X31") (pin "5") (pinfunction "5_5") (pintype "passive"))
    )
    (net (code "65") (name "Net-(FB26-Pad2)") (class "Default")
      (node (ref "FB26") (pin "2") (pinfunction "2_2") (pintype "passive"))
      (node (ref "RV12") (pin "2") (pinfunction "2_2") (pintype "passive"))
      (node (ref "X32") (pin "5") (pinfunction "5_5") (pintype "passive"))
    )
    (net (code "66") (name "Net-(FB27-Pad1)") (class "Default")
      (node (ref "FB27") (pin "1") (pinfunction "1_1") (pintype "passive"))
      (node (ref "RV30") (pin "2") (pinfunction "2_2") (pintype "passive"))
      (node (ref "X32") (pin "3") (pinfunction "3_3") (pintype "passive"))
    )
    (net (code "67") (name "Net-(FB28-Pad2)") (class "Default")
      (node (ref "FB28") (pin "2") (pinfunction "2_2") (pintype "passive"))
      (node (ref "P1") (pin "5") (pinfunction "5_5") (pintype "passive"))
      (node (ref "RV17") (pin "1") (pinfunction "1_1") (pintype "passive"))
    )
    (net (code "68") (name "Net-(FB29-Pad2)") (class "Default")
      (node (ref "FB29") (pin "2") (pinfunction "2_2") (pintype "passive"))
      (node (ref "P2") (pin "9") (pinfunction "9_9") (pintype "passive"))
      (node (ref "RV23") (pin "2") (pinfunction "2_2") (pintype "passive"))
    )
    (net (code "69") (name "Net-(FB30-Pad1)") (class "Default")
      (node (ref "FB30") (pin "1") (pinfunction "1_1") (pintype "passive"))
      (node (ref "P2") (pin "10") (pinfunction "10_10") (pintype "passive"))
      (node (ref "RV19") (pin "1") (pinfunction "1_1") (pintype "passive"))
    )
    (net (code "70") (name "Net-(FB31-Pad2)") (class "Default")
      (node (ref "FB31") (pin "2") (pinfunction "2_2") (pintype "passive"))
      (node (ref "P2") (pin "7") (pinfunction "7_7") (pintype "passive"))
      (node (ref "RV32") (pin "2") (pinfunction "2_2") (pintype "passive"))
    )
    (net (code "71") (name "Net-(FB32-Pad2)") (class "Default")
      (node (ref "FB32") (pin "2") (pinfunction "2_2") (pintype "passive"))
      (node (ref "P2") (pin "5") (pinfunction "5_5") (pintype "passive"))
      (node (ref "RV24") (pin "2") (pinfunction "2_2") (pintype "passive"))
    )
    (net (code "72") (name "Net-(L1-Pad1)") (class "Default")
      (node (ref "L1") (pin "1") (pinfunction "1_1") (pintype "passive"))
      (node (ref "X33") (pin "1") (pinfunction "1_1") (pintype "passive"))
    )
    (net (code "73") (name "Net-(X33C-1)") (class "Default")
      (node (ref "L4") (pin "1") (pinfunction "1_1") (pintype "passive"))
      (node (ref "X33") (pin "3") (pinfunction "1_3") (pintype "passive"))
    )
    (net (code "74") (name "VBED") (class "Default")
      (node (ref "C54") (pin "1") (pinfunction "1_1") (pintype "passive"))
      (node (ref "C62") (pin "1") (pinfunction "1_1") (pintype "passive"))
      (node (ref "C66") (pin "+") (pinfunction "+_+") (pintype "passive"))
      (node (ref "D7") (pin "C") (pinfunction "C_C") (pintype "passive"))
      (node (ref "F4") (pin "P$2") (pinfunction "2_P$2") (pintype "passive"))
    )
    (net (code "75") (name "VCC") (class "Default")
      (node (ref "C78") (pin "2") (pinfunction "2_2") (pintype "passive"))
      (node (ref "C92") (pin "2") (pinfunction "2_2") (pintype "passive"))
      (node (ref "C93") (pin "2") (pinfunction "2_2") (pintype "passive"))
      (node (ref "C94") (pin "2") (pinfunction "2_2") (pintype "passive"))
      (node (ref "C95") (pin "2") (pinfunction "2_2") (pintype "passive"))
      (node (ref "C97") (pin "1") (pinfunction "1_1") (pintype "passive"))
      (node (ref "P1") (pin "1") (pinfunction "1_1") (pintype "passive"))
      (node (ref "R44") (pin "2") (pinfunction "2_2") (pintype "passive"))
      (node (ref "R45") (pin "2") (pinfunction "2_2") (pintype "passive"))
      (node (ref "X1") (pin "2") (pinfunction "S_2") (pintype "passive"))
      (node (ref "X10") (pin "1") (pinfunction "S_1") (pintype "passive"))
      (node (ref "X18") (pin "2") (pinfunction "2_2") (pintype "passive"))
      (node (ref "X20") (pin "1") (pinfunction "1_1") (pintype "passive"))
      (node (ref "X31") (pin "1") (pinfunction "1_1") (pintype "passive"))
      (node (ref "X32") (pin "1") (pinfunction "1_1") (pintype "passive"))
      (node (ref "X34") (pin "1") (pinfunction "1_1") (pintype "passive"))
      (node (ref "X39") (pin "1") (pinfunction "1_1") (pintype "passive"))
      (node (ref "X5") (pin "2") (pinfunction "S_2") (pintype "passive"))
    )
    (net (code "76") (name "VHEAT") (class "Default")
      (node (ref "C60") (pin "1") (pinfunction "1_1") (pintype "passive"))
      (node (ref "C65") (pin "+") (pinfunction "+_+") (pintype "passive"))
      (node (ref "D8") (pin "K") (pinfunction "K_K") (pintype "passive"))
      (node (ref "F3") (pin "P$2") (pinfunction "P$2_P$2") (pintype "passive"))
    )
    (net (code "77") (name "VMOT") (class "Default")
      (node (ref "D2") (pin "K") (pinfunction "K_K") (pintype "passive"))
      (node (ref "F2") (pin "P$2") (pinfunction "P$2_P$2") (pintype "passive"))
      (node (ref "X30") (pin "2") (pinfunction "S_2") (pintype "passive"))
    )
  )
)
